# Jaguar.net
KiCad netlist of a schematic drawn in EAGLE
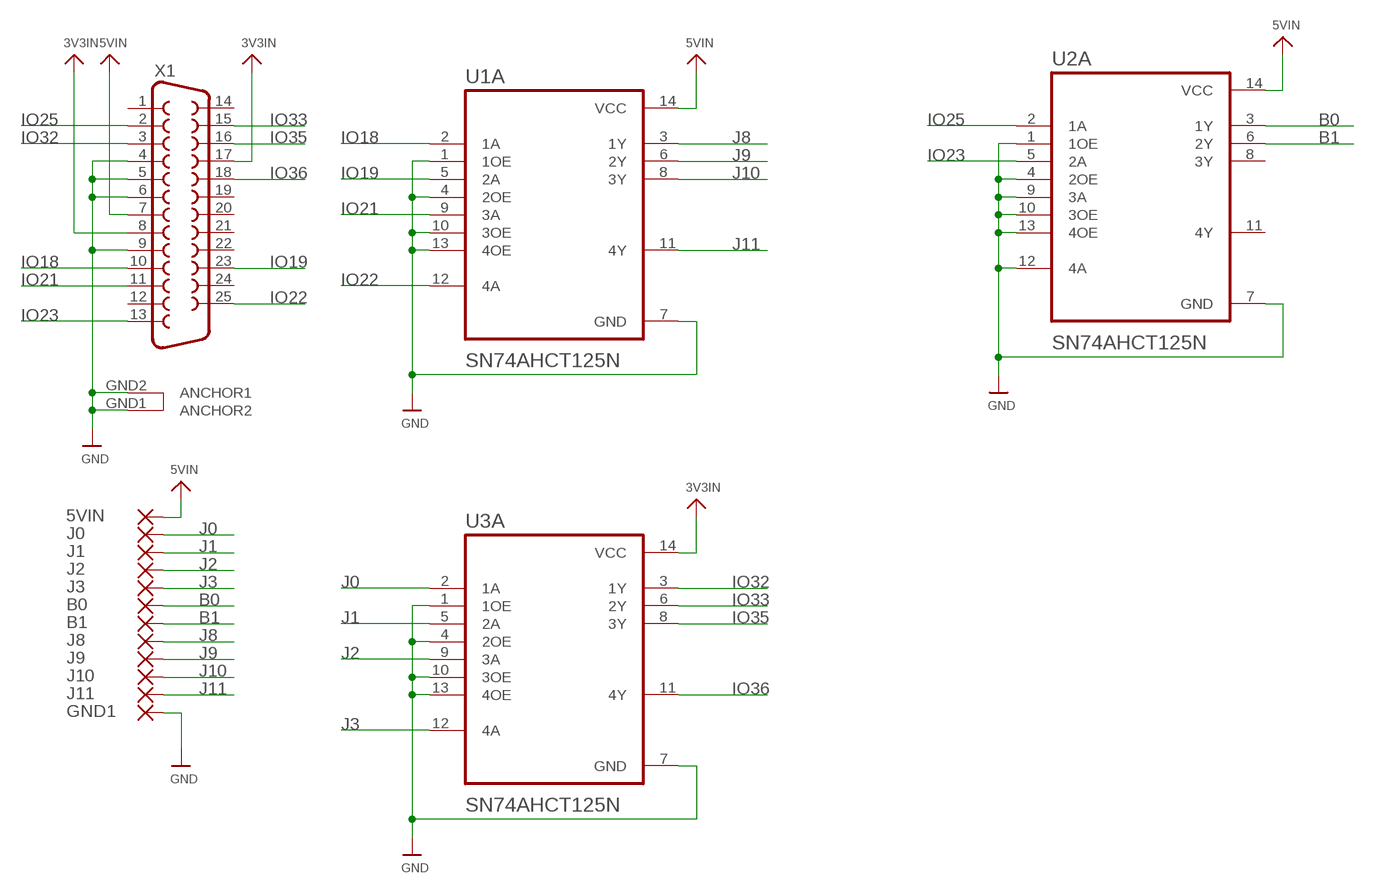
[diagram p0: schematic, sheet 1]

(export (version "E")
  (design (tool "Eeschema 10.0.6"))
  (components
    (comp (ref "5VIN")
      (value "SMD5")
      (footprint "eagle-import:SMD2,54-5,08")
      (libsource (lib "eagle-import") (part "SMD5"))
    )
    (comp (ref "B0")
      (value "SMD5")
      (footprint "eagle-import:SMD2,54-5,08")
      (libsource (lib "eagle-import") (part "SMD5"))
    )
    (comp (ref "B1")
      (value "SMD5")
      (footprint "eagle-import:SMD2,54-5,08")
      (libsource (lib "eagle-import") (part "SMD5"))
    )
    (comp (ref "GND1")
      (value "SMD5")
      (footprint "eagle-import:SMD2,54-5,08")
      (libsource (lib "eagle-import") (part "SMD5"))
    )
    (comp (ref "J0")
      (value "SMD5")
      (footprint "eagle-import:SMD2,54-5,08")
      (libsource (lib "eagle-import") (part "SMD5"))
    )
    (comp (ref "J1")
      (value "SMD5")
      (footprint "eagle-import:SMD2,54-5,08")
      (libsource (lib "eagle-import") (part "SMD5"))
    )
    (comp (ref "J2")
      (value "SMD5")
      (footprint "eagle-import:SMD2,54-5,08")
      (libsource (lib "eagle-import") (part "SMD5"))
    )
    (comp (ref "J3")
      (value "SMD5")
      (footprint "eagle-import:SMD2,54-5,08")
      (libsource (lib "eagle-import") (part "SMD5"))
    )
    (comp (ref "J8")
      (value "SMD5")
      (footprint "eagle-import:SMD2,54-5,08")
      (libsource (lib "eagle-import") (part "SMD5"))
    )
    (comp (ref "J9")
      (value "SMD5")
      (footprint "eagle-import:SMD2,54-5,08")
      (libsource (lib "eagle-import") (part "SMD5"))
    )
    (comp (ref "J10")
      (value "SMD5")
      (footprint "eagle-import:SMD2,54-5,08")
      (libsource (lib "eagle-import") (part "SMD5"))
    )
    (comp (ref "J11")
      (value "SMD5")
      (footprint "eagle-import:SMD2,54-5,08")
      (libsource (lib "eagle-import") (part "SMD5"))
    )
    (comp (ref "U1A")
      (value "SN74AHCT125N")
      (footprint "eagle-import:DIP794W45P254L1969H508Q14")
      (fields (field (name "MF") "Texas Instruments"))
      (libsource (lib "eagle-import") (part "SN74AHCT125N"))
    )
    (comp (ref "U2A")
      (value "SN74AHCT125N")
      (footprint "eagle-import:DIP794W45P254L1969H508Q14")
      (fields (field (name "MF") "Texas Instruments"))
      (libsource (lib "eagle-import") (part "SN74AHCT125N"))
    )
    (comp (ref "U3A")
      (value "SN74AHCT125N")
      (footprint "eagle-import:DIP794W45P254L1969H508Q14")
      (fields (field (name "MF") "Texas Instruments"))
      (libsource (lib "eagle-import") (part "SN74AHCT125N"))
    )
    (comp (ref "X1")
      (value "DB25_FEMALEHP")
      (footprint "eagle-import:F25HP")
      (libsource (lib "eagle-import") (part "DB25_FEMALEHP"))
    )
  )
  (nets
    (net (code "1") (name "/B0") (class "Default")
      (node (ref "B0") (pin "1") (pinfunction "P_1") (pintype "passive"))
      (node (ref "U2A") (pin "3") (pinfunction "1Y_3") (pintype "output"))
    )
    (net (code "2") (name "/B1") (class "Default")
      (node (ref "B1") (pin "1") (pinfunction "P_1") (pintype "passive"))
      (node (ref "U2A") (pin "6") (pinfunction "2Y_6") (pintype "output"))
    )
    (net (code "3") (name "/IO18") (class "Default")
      (node (ref "U1A") (pin "2") (pinfunction "1A_2") (pintype "input"))
      (node (ref "X1") (pin "10") (pinfunction "10_10") (pintype "passive"))
    )
    (net (code "4") (name "/IO19") (class "Default")
      (node (ref "U1A") (pin "5") (pinfunction "2A_5") (pintype "input"))
      (node (ref "X1") (pin "23") (pinfunction "23_23") (pintype "passive"))
    )
    (net (code "5") (name "/IO21") (class "Default")
      (node (ref "U1A") (pin "9") (pinfunction "3A_9") (pintype "input"))
      (node (ref "X1") (pin "11") (pinfunction "11_11") (pintype "passive"))
    )
    (net (code "6") (name "/IO22") (class "Default")
      (node (ref "U1A") (pin "12") (pinfunction "4A_12") (pintype "bidirectional"))
      (node (ref "X1") (pin "25") (pinfunction "25_25") (pintype "passive"))
    )
    (net (code "7") (name "/IO23") (class "Default")
      (node (ref "U2A") (pin "5") (pinfunction "2A_5") (pintype "input"))
      (node (ref "X1") (pin "13") (pinfunction "13_13") (pintype "passive"))
    )
    (net (code "8") (name "/IO25") (class "Default")
      (node (ref "U2A") (pin "2") (pinfunction "1A_2") (pintype "input"))
      (node (ref "X1") (pin "2") (pinfunction "2_2") (pintype "passive"))
    )
    (net (code "9") (name "/IO32") (class "Default")
      (node (ref "U3A") (pin "3") (pinfunction "1Y_3") (pintype "output"))
      (node (ref "X1") (pin "3") (pinfunction "3_3") (pintype "passive"))
    )
    (net (code "10") (name "/IO33") (class "Default")
      (node (ref "U3A") (pin "6") (pinfunction "2Y_6") (pintype "output"))
      (node (ref "X1") (pin "15") (pinfunction "15_15") (pintype "passive"))
    )
    (net (code "11") (name "/IO35") (class "Default")
      (node (ref "U3A") (pin "8") (pinfunction "3Y_8") (pintype "output"))
      (node (ref "X1") (pin "16") (pinfunction "16_16") (pintype "passive"))
    )
    (net (code "12") (name "/IO36") (class "Default")
      (node (ref "U3A") (pin "11") (pinfunction "4Y_11") (pintype "output"))
      (node (ref "X1") (pin "18") (pinfunction "18_18") (pintype "passive"))
    )
    (net (code "13") (name "/J0") (class "Default")
      (node (ref "J0") (pin "1") (pinfunction "P_1") (pintype "passive"))
      (node (ref "U3A") (pin "2") (pinfunction "1A_2") (pintype "input"))
    )
    (net (code "14") (name "/J1") (class "Default")
      (node (ref "J1") (pin "1") (pinfunction "P_1") (pintype "passive"))
      (node (ref "U3A") (pin "5") (pinfunction "2A_5") (pintype "input"))
    )
    (net (code "15") (name "/J2") (class "Default")
      (node (ref "J2") (pin "1") (pinfunction "P_1") (pintype "passive"))
      (node (ref "U3A") (pin "9") (pinfunction "3A_9") (pintype "input"))
    )
    (net (code "16") (name "/J3") (class "Default")
      (node (ref "J3") (pin "1") (pinfunction "P_1") (pintype "passive"))
      (node (ref "U3A") (pin "12") (pinfunction "4A_12") (pintype "bidirectional"))
    )
    (net (code "17") (name "/J8") (class "Default")
      (node (ref "J8") (pin "1") (pinfunction "P_1") (pintype "passive"))
      (node (ref "U1A") (pin "3") (pinfunction "1Y_3") (pintype "output"))
    )
    (net (code "18") (name "/J9") (class "Default")
      (node (ref "J9") (pin "1") (pinfunction "P_1") (pintype "passive"))
      (node (ref "U1A") (pin "6") (pinfunction "2Y_6") (pintype "output"))
    )
    (net (code "19") (name "/J10") (class "Default")
      (node (ref "J10") (pin "1") (pinfunction "P_1") (pintype "passive"))
      (node (ref "U1A") (pin "8") (pinfunction "3Y_8") (pintype "output"))
    )
    (net (code "20") (name "/J11") (class "Default")
      (node (ref "J11") (pin "1") (pinfunction "P_1") (pintype "passive"))
      (node (ref "U1A") (pin "11") (pinfunction "4Y_11") (pintype "output"))
    )
    (net (code "21") (name "3V3IN") (class "Default")
      (node (ref "U3A") (pin "14") (pinfunction "VCC_14") (pintype "power_in"))
      (node (ref "X1") (pin "17") (pinfunction "17_17") (pintype "passive"))
      (node (ref "X1") (pin "8") (pinfunction "8_8") (pintype "passive"))
    )
    (net (code "22") (name "5VIN") (class "Default")
      (node (ref "5VIN") (pin "1") (pinfunction "P_1") (pintype "passive"))
      (node (ref "U1A") (pin "14") (pinfunction "VCC_14") (pintype "power_in"))
      (node (ref "U2A") (pin "14") (pinfunction "VCC_14") (pintype "power_in"))
      (node (ref "X1") (pin "7") (pinfunction "7_7") (pintype "passive"))
    )
    (net (code "23") (name "GND") (class "Default")
      (node (ref "GND1") (pin "1") (pinfunction "P_1") (pintype "passive"))
      (node (ref "U1A") (pin "1") (pinfunction "1OE_1") (pintype "input"))
      (node (ref "U1A") (pin "10") (pinfunction "3OE_10") (pintype "input"))
      (node (ref "U1A") (pin "13") (pinfunction "4OE_13") (pintype "input"))
      (node (ref "U1A") (pin "4") (pinfunction "2OE_4") (pintype "input"))
      (node (ref "U1A") (pin "7") (pinfunction "GND_7") (pintype "power_in"))
      (node (ref "U2A") (pin "1") (pinfunction "1OE_1") (pintype "input"))
      (node (ref "U2A") (pin "10") (pinfunction "3OE_10") (pintype "input"))
      (node (ref "U2A") (pin "12") (pinfunction "4A_12") (pintype "bidirectional"))
      (node (ref "U2A") (pin "13") (pinfunction "4OE_13") (pintype "input"))
      (node (ref "U2A") (pin "4") (pinfunction "2OE_4") (pintype "input"))
      (node (ref "U2A") (pin "7") (pinfunction "GND_7") (pintype "power_in"))
      (node (ref "U2A") (pin "9") (pinfunction "3A_9") (pintype "input"))
      (node (ref "U3A") (pin "1") (pinfunction "1OE_1") (pintype "input"))
      (node (ref "U3A") (pin "10") (pinfunction "3OE_10") (pintype "input"))
      (node (ref "U3A") (pin "13") (pinfunction "4OE_13") (pintype "input"))
      (node (ref "U3A") (pin "4") (pinfunction "2OE_4") (pintype "input"))
      (node (ref "U3A") (pin "7") (pinfunction "GND_7") (pintype "power_in"))
      (node (ref "X1") (pin "4") (pinfunction "4_4") (pintype "passive"))
      (node (ref "X1") (pin "5") (pinfunction "5_5") (pintype "passive"))
      (node (ref "X1") (pin "6") (pinfunction "6_6") (pintype "passive"))
      (node (ref "X1") (pin "9") (pinfunction "9_9") (pintype "passive"))
      (node (ref "X1") (pin "GND1") (pinfunction "ANCHOR2_GND1") (pintype "bidirectional"))
      (node (ref "X1") (pin "GND2") (pinfunction "ANCHOR1_GND2") (pintype "bidirectional"))
    )
    (net (code "24") (name "unconnected-(U2A-3Y-Pad8)") (class "Default")
      (node (ref "U2A") (pin "8") (pinfunction "3Y_8") (pintype "output"))
    )
    (net (code "25") (name "unconnected-(U2A-4Y-Pad11)") (class "Default")
      (node (ref "U2A") (pin "11") (pinfunction "4Y_11") (pintype "output"))
    )
    (net (code "26") (name "unconnected-(X1-Pad1)") (class "Default")
      (node (ref "X1") (pin "1") (pinfunction "1_1") (pintype "passive"))
    )
    (net (code "27") (name "unconnected-(X1-Pad12)") (class "Default")
      (node (ref "X1") (pin "12") (pinfunction "12_12") (pintype "passive"))
    )
    (net (code "28") (name "unconnected-(X1-Pad14)") (class "Default")
      (node (ref "X1") (pin "14") (pinfunction "14_14") (pintype "passive"))
    )
    (net (code "29") (name "unconnected-(X1-Pad19)") (class "Default")
      (node (ref "X1") (pin "19") (pinfunction "19_19") (pintype "passive"))
    )
    (net (code "30") (name "unconnected-(X1-Pad20)") (class "Default")
      (node (ref "X1") (pin "20") (pinfunction "20_20") (pintype "passive"))
    )
    (net (code "31") (name "unconnected-(X1-Pad21)") (class "Default")
      (node (ref "X1") (pin "21") (pinfunction "21_21") (pintype "passive"))
    )
    (net (code "32") (name "unconnected-(X1-Pad22)") (class "Default")
      (node (ref "X1") (pin "22") (pinfunction "22_22") (pintype "passive"))
    )
    (net (code "33") (name "unconnected-(X1-Pad24)") (class "Default")
      (node (ref "X1") (pin "24") (pinfunction "24_24") (pintype "passive"))
    )
  )
)
